# LMR514203_3V.net
KiCad netlist of a schematic drawn in Altium Designer
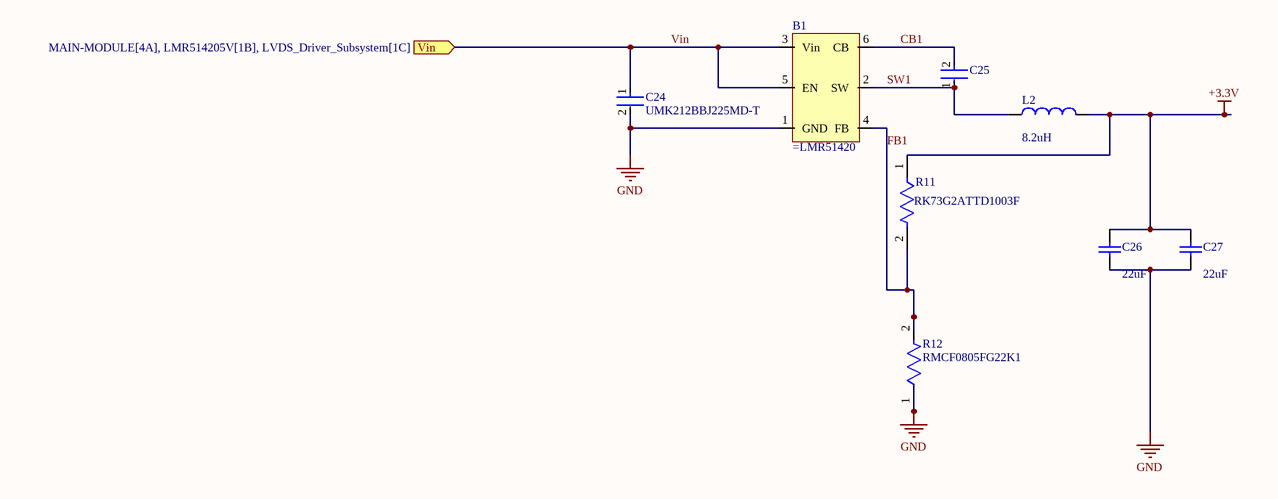
[diagram p0: LMR514203.3V.SchDoc]

(export (version "E")
  (design (tool "Eeschema 10.0.6"))
  (components
    (comp (ref "B1") (value "~") (footprint "LMR51420IC") (libsource (lib "LMR51420") (part "Component_1")))
    (comp (ref "C24")
      (value "UMK212BBJ225MD-T")
      (footprint "FP-0805-L_2_0_0_2-W_1_25-IPC_A")
      (description "Multilayer Ceramic Capacitor 2.2uF 50V X5R 20% SMD 0803 T/R")
      (fields (field (name "TOLERANCE") "20%"))
      (libsource (lib "Altium Content Vault") (part "02cd4be3c70576c341d710602a673aa"))
    )
    (comp (ref "C25")
      (value "C0603C104K4PAC7867")
      (footprint "CAP CER 0.1UF 16V X7R 0603")
      (description "CAP CER 0.1UF 16V X5R 0603")
      (fields
        (field (name "OCTOPART") "https://octopart.com/c0603c104k4pactu-kemet-12592163")
        (field (name "MANUFACTURER") "KEMET")
      )
      (libsource (lib "Miscellaneous Devices") (part "b4654b650e69147ec39a6b967a45e02"))
    )
    (comp (ref "C26")
      (value "22uF")
      (footprint "Cap22uF_C1206C226M4PAC7800")
      (description "Capacitor")
      (fields (field (name "Comment") "Comment") (field (name "PUBLISHER") "Altium Limited"))
      (libsource (lib "Miscellaneous Devices") (part "Cap"))
    )
    (comp (ref "C27")
      (value "22uF")
      (footprint "Cap22uF_C1206C226M4PAC7800")
      (description "Capacitor")
      (fields (field (name "Comment") "Comment") (field (name "PUBLISHER") "Altium Limited"))
      (libsource (lib "Miscellaneous Devices") (part "Cap"))
    )
    (comp (ref "L2")
      (value "8.2uH")
      (footprint "MSS1246H-103MED 10uH")
      (description "Inductor")
      (fields (field (name "Comment") "MSS1260H-822MED") (field (name "PUBLISHER") "Altium Limited"))
      (libsource (lib "Miscellaneous Devices") (part "Inductor"))
    )
    (comp (ref "R11")
      (value "RK73G2ATTD1003F")
      (footprint "FP-RK73G2A-IPC_A")
      (description "100kΩ ±1% 0.125W Chip Resistor 0805 Thick Film AEC-Q200 Qualified")
      (fields (field (name "TOLERANCE") "1%"))
      (libsource (lib "Altium Content Vault") (part "1029c3af85768c4190bb7ad29bc67b5"))
    )
    (comp (ref "R12")
      (value "RMCF0805FG22K1")
      (footprint "FP-RMCF0805-IPC_B")
      (description "22.1kΩ ±1% 0.125W 0805 Thick Film Chip Resistor AEC-Q200 compliant")
      (fields (field (name "TOLERANCE") "1%"))
      (libsource (lib "Altium Content Vault") (part "1029c3af85768c4190bb7ad29bc67b5"))
    )
  )
  (nets
    (net (code "1") (name "+3.3V") (class "Default")
      (node (ref "C26") (pin "2") (pinfunction "2_2") (pintype "passive"))
      (node (ref "C27") (pin "2") (pinfunction "2_2") (pintype "passive"))
      (node (ref "L2") (pin "2") (pinfunction "2_2") (pintype "passive"))
      (node (ref "R11") (pin "1") (pinfunction "1_1") (pintype "passive"))
    )
    (net (code "2") (name "/CB1") (class "Default")
      (node (ref "B1") (pin "6") (pinfunction "CB_6") (pintype "passive"))
      (node (ref "C25") (pin "2") (pinfunction "2_2") (pintype "passive"))
    )
    (net (code "3") (name "/FB1") (class "Default")
      (node (ref "B1") (pin "4") (pinfunction "FB_4") (pintype "passive"))
      (node (ref "R11") (pin "2") (pinfunction "2_2") (pintype "passive"))
      (node (ref "R12") (pin "2") (pinfunction "2_2") (pintype "passive"))
    )
    (net (code "4") (name "/SW1") (class "Default")
      (node (ref "B1") (pin "2") (pinfunction "SW_2") (pintype "passive"))
      (node (ref "C25") (pin "1") (pinfunction "1_1") (pintype "passive"))
      (node (ref "L2") (pin "1") (pinfunction "1_1") (pintype "passive"))
    )
    (net (code "5") (name "/Vin") (class "Default")
      (node (ref "B1") (pin "3") (pinfunction "Vin_3") (pintype "passive"))
      (node (ref "B1") (pin "5") (pinfunction "EN_5") (pintype "passive"))
      (node (ref "C24") (pin "1") (pinfunction "1_1") (pintype "passive"))
    )
    (net (code "6") (name "GND") (class "Default")
      (node (ref "B1") (pin "1") (pinfunction "GND_1") (pintype "passive"))
      (node (ref "C24") (pin "2") (pinfunction "2_2") (pintype "passive"))
      (node (ref "C26") (pin "1") (pinfunction "1_1") (pintype "passive"))
      (node (ref "C27") (pin "1") (pinfunction "1_1") (pintype "passive"))
      (node (ref "R12") (pin "1") (pinfunction "1_1") (pintype "passive"))
    )
  )
)
